# PSU_3V3_LD29300.net
KiCad netlist of a schematic drawn in Altium Designer
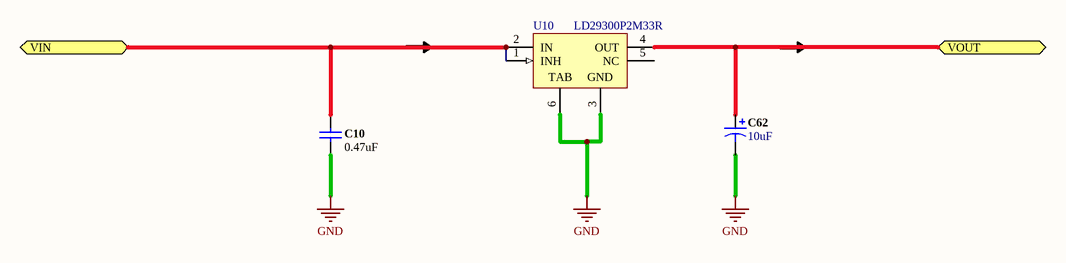
[diagram p0: PSU_3V3_LD29300.SchDoc]

(export (version "E")
  (design (tool "Eeschema 10.0.6"))
  (components
    (comp (ref "C10")
      (value "0.47uF")
      (footprint "0805C-GENERIC")
      (description "Capacitor, Ceramic, 10% 10V 0805 X7R")
      (fields (field (name "CAPACITANCE") "0.47uF") (field (name "TOLERANCE") "10 %"))
      (libsource (lib "altium-import") (part "root_0_CAP-NP_"))
    )
    (comp (ref "C62")
      (value "10uF")
      (footprint "AVX-CAPC3528_V")
      (description "Capacitor, Tantalum, 10uF 10% 20V MCCT-B (3528) - TAJB106K020RNJ")
      (fields (field (name "PARTNUMBER") "TAJB106K020RNJ") (field (name "MANUFACTURER") "AVX"))
      (libsource (lib "Arduino - FPGA Development Board") (part "CMP-0279-00001-1"))
    )
    (comp (ref "U10")
      (value "LD29300P2M33R")
      (footprint "P2PAK/A_N")
      (description "3A, Very Low-Drop Voltage Regulators, 3.3V, 6-Pin P2PAK/A")
      (libsource (lib "STMicroelectronics Power Management Linear Regulator") (part "LD29300P2M33R"))
    )
  )
  (nets
    (net (code "1") (name "/VIN") (class "Default")
      (node (ref "C10") (pin "1") (pinfunction "1_1") (pintype "passive"))
      (node (ref "U10") (pin "1") (pinfunction "INH_1") (pintype "input"))
      (node (ref "U10") (pin "2") (pinfunction "IN_2") (pintype "power_in"))
    )
    (net (code "2") (name "/VOUT") (class "Default")
      (node (ref "C62") (pin "1") (pinfunction "1_1") (pintype "passive"))
      (node (ref "U10") (pin "4") (pinfunction "OUT_4") (pintype "power_in"))
    )
    (net (code "3") (name "GND") (class "Default")
      (node (ref "C10") (pin "2") (pinfunction "2_2") (pintype "passive"))
      (node (ref "C62") (pin "2") (pinfunction "2_2") (pintype "passive"))
      (node (ref "U10") (pin "3") (pinfunction "GND_3") (pintype "power_in"))
      (node (ref "U10") (pin "6") (pinfunction "TAB_6") (pintype "passive"))
    )
    (net (code "4") (name "unconnected-(U10-NC-Pad5)") (class "Default")
      (node (ref "U10") (pin "5") (pinfunction "NC_5") (pintype "passive"))
    )
  )
)
